# MCU.net
KiCad netlist of a schematic drawn in Altium Designer
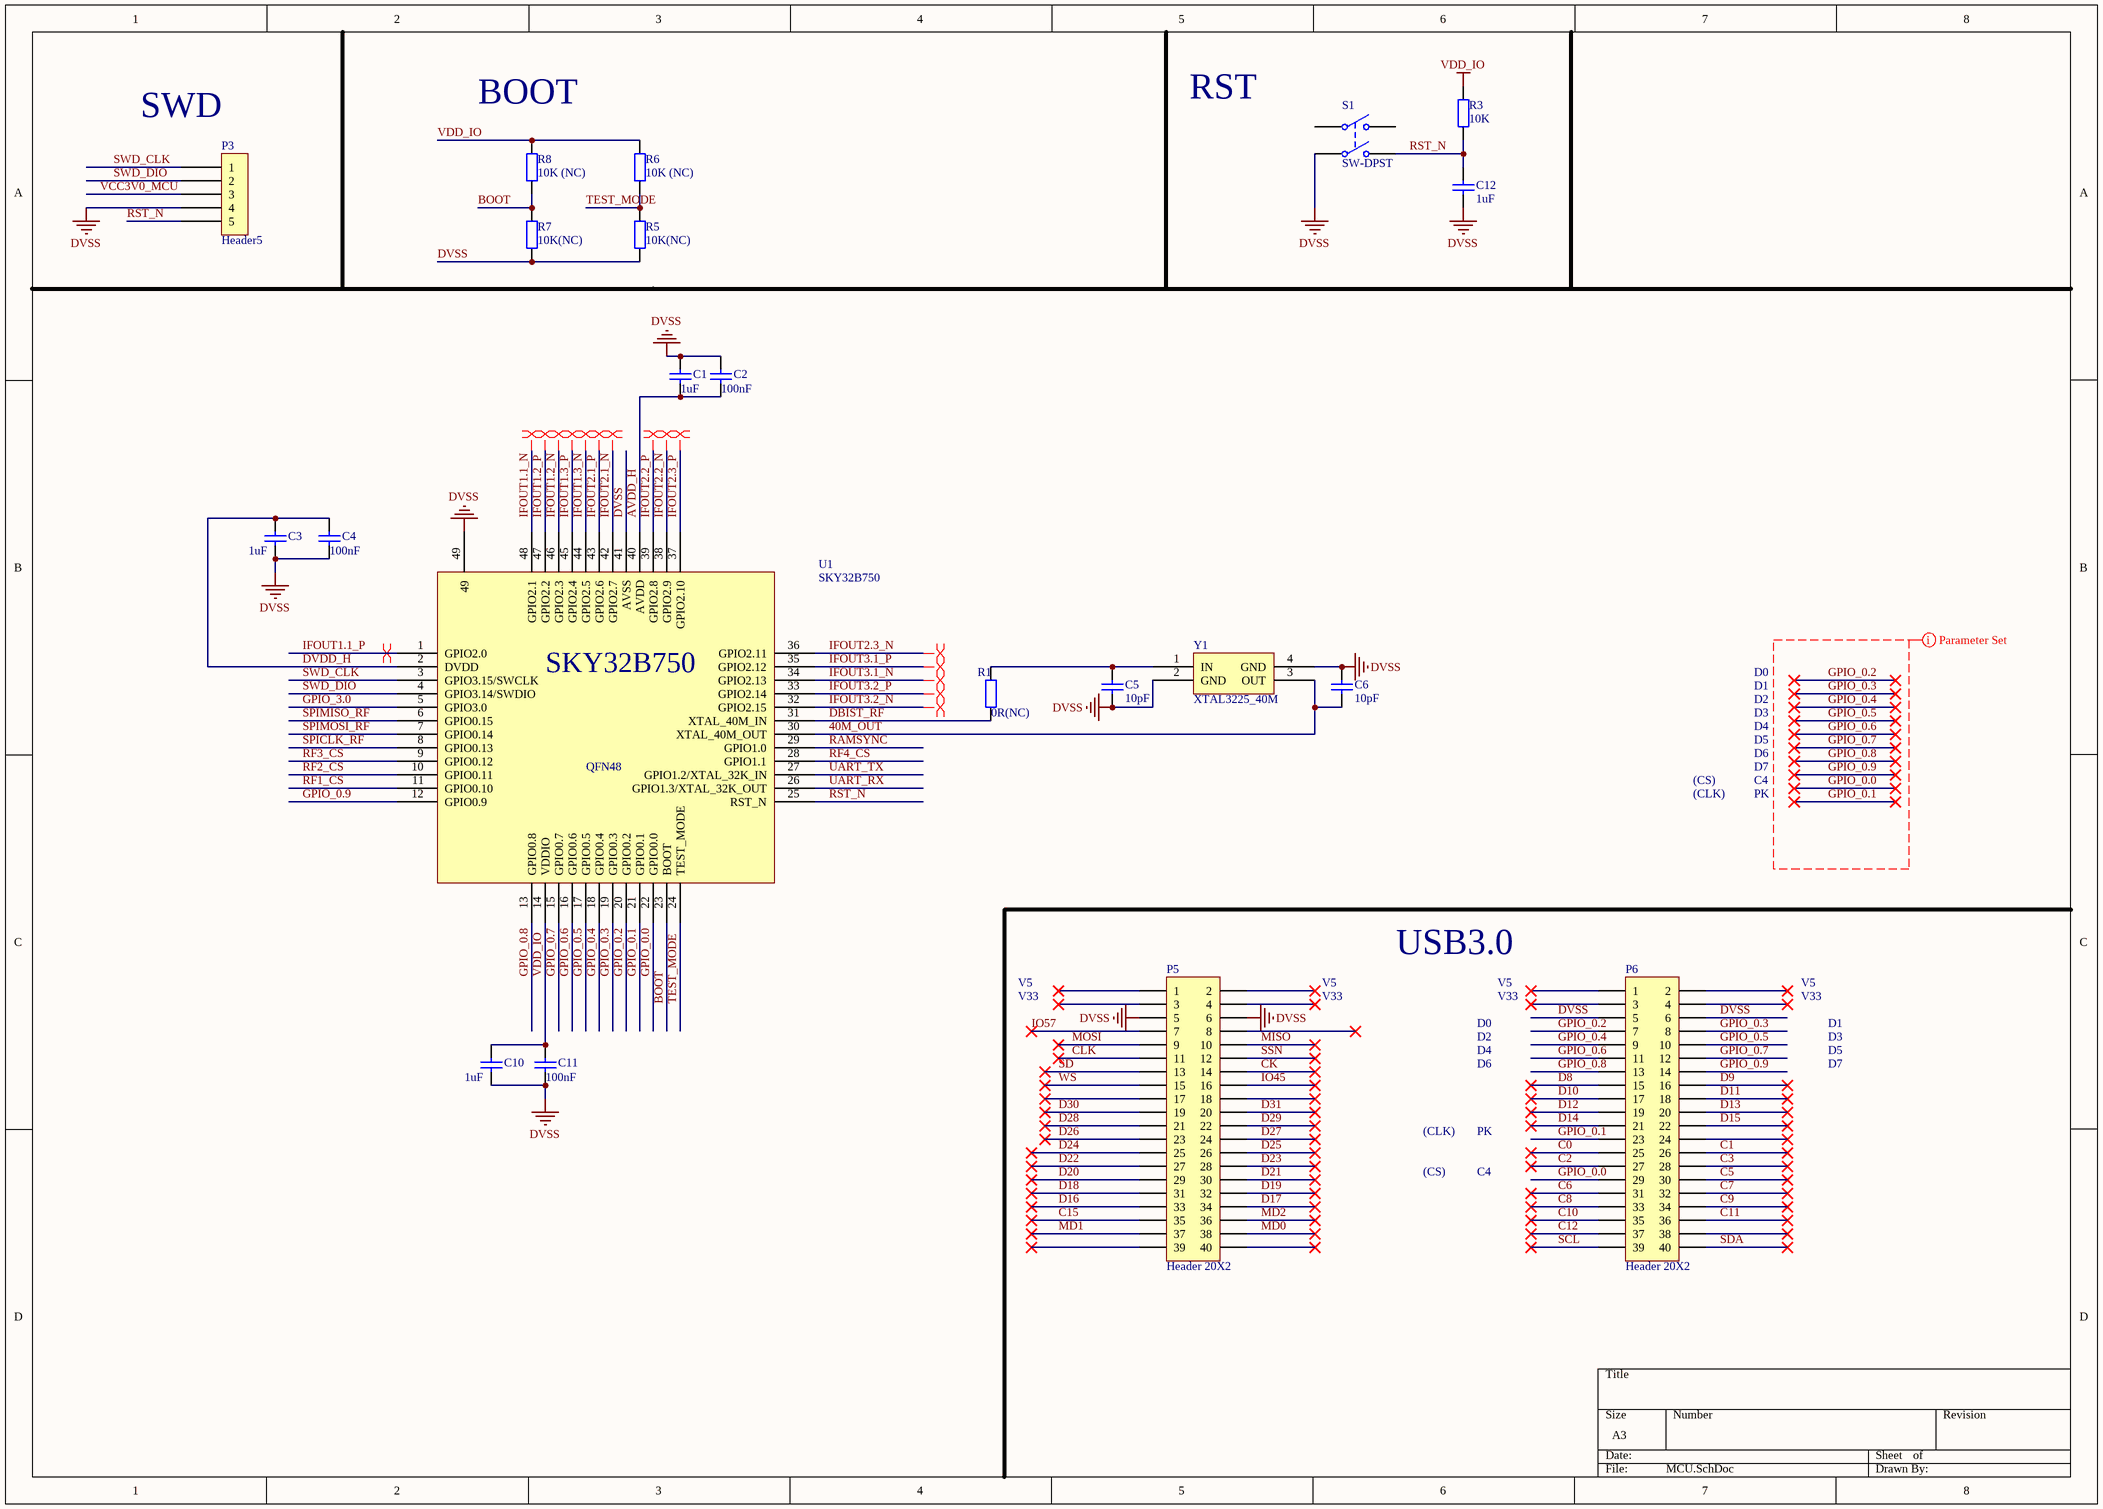
[diagram p0: MCU.SchDoc]

(export (version "E")
  (design (tool "Eeschema 10.0.6"))
  (components
    (comp (ref "C1")
      (value "1uF")
      (footprint "R0603")
      (description "CAP, CERM, 4.7nF, 100 V, +/- 5%, X7R, 0603")
      (fields (field (name "PUBLISHER") "Altium Limited"))
      (libsource (lib "SKY1311T-READER-V1.0_1") (part "Cap"))
    )
    (comp (ref "C2")
      (value "100nF")
      (footprint "R0603")
      (description "CAP, CERM, 4.7nF, 100 V, +/- 5%, X7R, 0603")
      (fields (field (name "PUBLISHER") "Altium Limited"))
      (libsource (lib "SKY1311T-READER-V1.0_1") (part "Cap"))
    )
    (comp (ref "C3")
      (value "1uF")
      (footprint "R0603")
      (description "CAP, CERM, 4.7nF, 100 V, +/- 5%, X7R, 0603")
      (fields (field (name "PUBLISHER") "Altium Limited"))
      (libsource (lib "SKY1311T-READER-V1.0_1") (part "Cap"))
    )
    (comp (ref "C4")
      (value "100nF")
      (footprint "R0603")
      (description "CAP, CERM, 4.7nF, 100 V, +/- 5%, X7R, 0603")
      (fields (field (name "PUBLISHER") "Altium Limited"))
      (libsource (lib "SKY1311T-READER-V1.0_1") (part "Cap"))
    )
    (comp (ref "C5")
      (value "10pF")
      (footprint "R0603")
      (description "Capacitor")
      (fields (field (name "PUBLISHER") "Altium Limited"))
      (libsource (lib "Miscellaneous Devices") (part "Cap"))
    )
    (comp (ref "C6")
      (value "10pF")
      (footprint "R0603")
      (description "Capacitor")
      (fields (field (name "PUBLISHER") "Altium Limited"))
      (libsource (lib "Miscellaneous Devices") (part "Cap"))
    )
    (comp (ref "C10")
      (value "1uF")
      (footprint "R0603")
      (description "CAP, CERM, 4.7nF, 100 V, +/- 5%, X7R, 0603")
      (fields (field (name "PUBLISHER") "Altium Limited"))
      (libsource (lib "SKY1311T-READER-V1.0_1") (part "Cap"))
    )
    (comp (ref "C11")
      (value "100nF")
      (footprint "R0603")
      (description "CAP, CERM, 4.7nF, 100 V, +/- 5%, X7R, 0603")
      (fields (field (name "PUBLISHER") "Altium Limited"))
      (libsource (lib "SKY1311T-READER-V1.0_1") (part "Cap"))
    )
    (comp (ref "C12")
      (value "1uF")
      (footprint "R0603")
      (description "Capacitor")
      (fields (field (name "PUBLISHER") "Altium Limited"))
      (libsource (lib "Miscellaneous Devices") (part "Cap"))
    )
    (comp (ref "P3")
      (value "Header5")
      (footprint "HDR1X5")
      (libsource (lib "SKY32B750_OSPI_EVB1_V2.0") (part "Header5"))
    )
    (comp (ref "P5")
      (value "Header 20X2")
      (footprint "2X20_2_54_SMD")
      (description "Header, 20-Pin, Dual row")
      (fields (field (name "PUBLISHER") "Altium Limited"))
      (libsource (lib "Miscellaneous Connectors") (part "Header 20X2"))
    )
    (comp (ref "P6")
      (value "Header 20X2")
      (footprint "2X20_2_54_SMD")
      (description "Header, 20-Pin, Dual row")
      (fields (field (name "PUBLISHER") "Altium Limited"))
      (libsource (lib "Miscellaneous Connectors") (part "Header 20X2"))
    )
    (comp (ref "R1")
      (value "0R(NC)")
      (footprint "R0603")
      (description "Resistor")
      (fields (field (name "PUBLISHER") "Altium Limited"))
      (libsource (lib "Miscellaneous Devices") (part "Res2"))
    )
    (comp (ref "R3")
      (value "10K")
      (footprint "R0603")
      (description "Resistor")
      (fields (field (name "PUBLISHER") "Altium Limited"))
      (libsource (lib "Miscellaneous Devices") (part "Res2"))
    )
    (comp (ref "R5")
      (value "10K(NC)")
      (footprint "R0603")
      (description "Resistor")
      (fields (field (name "PUBLISHER") "Altium Limited"))
      (libsource (lib "") (part "Res2_1"))
    )
    (comp (ref "R6")
      (value "10K (NC)")
      (footprint "R0603")
      (description "Resistor")
      (fields (field (name "PUBLISHER") "Altium Limited"))
      (libsource (lib "") (part "Res2_1"))
    )
    (comp (ref "R7")
      (value "10K(NC)")
      (footprint "R0603")
      (description "Resistor")
      (fields (field (name "PUBLISHER") "Altium Limited"))
      (libsource (lib "") (part "Res2_1"))
    )
    (comp (ref "R8")
      (value "10K (NC)")
      (footprint "R0603")
      (description "Resistor")
      (fields (field (name "PUBLISHER") "Altium Limited"))
      (libsource (lib "") (part "Res2_1"))
    )
    (comp (ref "S1")
      (value "SW-DPST")
      (footprint "sw")
      (description "Double-Pole, Single-Throw Switch")
      (fields (field (name "PUBLISHER") "Altium Limited"))
      (libsource (lib "Miscellaneous Devices") (part "SW-DPST"))
    )
    (comp (ref "U1")
      (value "SKY32B750")
      (footprint "QFN48")
      (libsource (lib "SKY32B750_OSPI_EVB1_V2.0") (part "SYK32B750"))
    )
    (comp (ref "Y1")
      (value "XTAL3225_40M")
      (footprint "XTAL-3225")
      (libsource (lib "Schlib1") (part "XTAL3225"))
    )
  )
  (nets
    (net (code "1") (name "/40M_OUT") (class "Default")
      (node (ref "C6") (pin "2") (pinfunction "2_2") (pintype "passive"))
      (node (ref "U1") (pin "30") (pinfunction "XTAL_40M_OUT_30") (pintype "passive"))
      (node (ref "Y1") (pin "3") (pinfunction "OUT_3") (pintype "passive"))
    )
    (net (code "2") (name "/AVDD_H") (class "Default")
      (node (ref "C1") (pin "1") (pinfunction "1_1") (pintype "passive"))
      (node (ref "C2") (pin "1") (pinfunction "1_1") (pintype "passive"))
      (node (ref "U1") (pin "40") (pinfunction "AVDD_40") (pintype "passive"))
    )
    (net (code "3") (name "/BOOT") (class "Default")
      (node (ref "R7") (pin "1") (pinfunction "1_1") (pintype "passive"))
      (node (ref "R8") (pin "2") (pinfunction "2_2") (pintype "passive"))
      (node (ref "U1") (pin "23") (pinfunction "BOOT_23") (pintype "passive"))
    )
    (net (code "4") (name "/C0") (class "Default")
      (node (ref "P6") (pin "25") (pinfunction "25_25") (pintype "passive+no_connect"))
    )
    (net (code "5") (name "/C1") (class "Default")
      (node (ref "P6") (pin "26") (pinfunction "26_26") (pintype "passive+no_connect"))
    )
    (net (code "6") (name "/C2") (class "Default")
      (node (ref "P6") (pin "27") (pinfunction "27_27") (pintype "passive+no_connect"))
    )
    (net (code "7") (name "/C3") (class "Default")
      (node (ref "P6") (pin "28") (pinfunction "28_28") (pintype "passive+no_connect"))
    )
    (net (code "8") (name "/C5") (class "Default")
      (node (ref "P6") (pin "30") (pinfunction "30_30") (pintype "passive+no_connect"))
    )
    (net (code "9") (name "/C6") (class "Default")
      (node (ref "P6") (pin "31") (pinfunction "31_31") (pintype "passive+no_connect"))
    )
    (net (code "10") (name "/C7") (class "Default")
      (node (ref "P6") (pin "32") (pinfunction "32_32") (pintype "passive+no_connect"))
    )
    (net (code "11") (name "/C8") (class "Default")
      (node (ref "P6") (pin "33") (pinfunction "33_33") (pintype "passive+no_connect"))
    )
    (net (code "12") (name "/C9") (class "Default")
      (node (ref "P6") (pin "34") (pinfunction "34_34") (pintype "passive+no_connect"))
    )
    (net (code "13") (name "/C10") (class "Default")
      (node (ref "P6") (pin "35") (pinfunction "35_35") (pintype "passive+no_connect"))
    )
    (net (code "14") (name "/C11") (class "Default")
      (node (ref "P6") (pin "36") (pinfunction "36_36") (pintype "passive+no_connect"))
    )
    (net (code "15") (name "/C12") (class "Default")
      (node (ref "P6") (pin "37") (pinfunction "37_37") (pintype "passive+no_connect"))
    )
    (net (code "16") (name "/C15") (class "Default")
      (node (ref "P5") (pin "35") (pinfunction "35_35") (pintype "passive+no_connect"))
    )
    (net (code "17") (name "/CK") (class "Default")
      (node (ref "P5") (pin "14") (pinfunction "14_14") (pintype "passive+no_connect"))
    )
    (net (code "18") (name "/CLK") (class "Default")
      (node (ref "P5") (pin "11") (pinfunction "11_11") (pintype "passive+no_connect"))
    )
    (net (code "19") (name "/D8") (class "Default")
      (node (ref "P6") (pin "15") (pinfunction "15_15") (pintype "passive+no_connect"))
    )
    (net (code "20") (name "/D9") (class "Default")
      (node (ref "P6") (pin "16") (pinfunction "16_16") (pintype "passive+no_connect"))
    )
    (net (code "21") (name "/D10") (class "Default")
      (node (ref "P6") (pin "17") (pinfunction "17_17") (pintype "passive+no_connect"))
    )
    (net (code "22") (name "/D11") (class "Default")
      (node (ref "P6") (pin "18") (pinfunction "18_18") (pintype "passive+no_connect"))
    )
    (net (code "23") (name "/D12") (class "Default")
      (node (ref "P6") (pin "19") (pinfunction "19_19") (pintype "passive+no_connect"))
    )
    (net (code "24") (name "/D13") (class "Default")
      (node (ref "P6") (pin "20") (pinfunction "20_20") (pintype "passive+no_connect"))
    )
    (net (code "25") (name "/D14") (class "Default")
      (node (ref "P6") (pin "21") (pinfunction "21_21") (pintype "passive+no_connect"))
    )
    (net (code "26") (name "/D15") (class "Default")
      (node (ref "P6") (pin "22") (pinfunction "22_22") (pintype "passive+no_connect"))
    )
    (net (code "27") (name "/D16") (class "Default")
      (node (ref "P5") (pin "33") (pinfunction "33_33") (pintype "passive+no_connect"))
    )
    (net (code "28") (name "/D17") (class "Default")
      (node (ref "P5") (pin "34") (pinfunction "34_34") (pintype "passive+no_connect"))
    )
    (net (code "29") (name "/D18") (class "Default")
      (node (ref "P5") (pin "31") (pinfunction "31_31") (pintype "passive+no_connect"))
    )
    (net (code "30") (name "/D19") (class "Default")
      (node (ref "P5") (pin "32") (pinfunction "32_32") (pintype "passive+no_connect"))
    )
    (net (code "31") (name "/D20") (class "Default")
      (node (ref "P5") (pin "29") (pinfunction "29_29") (pintype "passive+no_connect"))
    )
    (net (code "32") (name "/D21") (class "Default")
      (node (ref "P5") (pin "30") (pinfunction "30_30") (pintype "passive+no_connect"))
    )
    (net (code "33") (name "/D22") (class "Default")
      (node (ref "P5") (pin "27") (pinfunction "27_27") (pintype "passive+no_connect"))
    )
    (net (code "34") (name "/D23") (class "Default")
      (node (ref "P5") (pin "28") (pinfunction "28_28") (pintype "passive+no_connect"))
    )
    (net (code "35") (name "/D24") (class "Default")
      (node (ref "P5") (pin "25") (pinfunction "25_25") (pintype "passive+no_connect"))
    )
    (net (code "36") (name "/D25") (class "Default")
      (node (ref "P5") (pin "26") (pinfunction "26_26") (pintype "passive+no_connect"))
    )
    (net (code "37") (name "/D26") (class "Default")
      (node (ref "P5") (pin "23") (pinfunction "23_23") (pintype "passive+no_connect"))
    )
    (net (code "38") (name "/D27") (class "Default")
      (node (ref "P5") (pin "24") (pinfunction "24_24") (pintype "passive+no_connect"))
    )
    (net (code "39") (name "/D28") (class "Default")
      (node (ref "P5") (pin "21") (pinfunction "21_21") (pintype "passive+no_connect"))
    )
    (net (code "40") (name "/D29") (class "Default")
      (node (ref "P5") (pin "22") (pinfunction "22_22") (pintype "passive+no_connect"))
    )
    (net (code "41") (name "/D30") (class "Default")
      (node (ref "P5") (pin "19") (pinfunction "19_19") (pintype "passive+no_connect"))
    )
    (net (code "42") (name "/D31") (class "Default")
      (node (ref "P5") (pin "20") (pinfunction "20_20") (pintype "passive+no_connect"))
    )
    (net (code "43") (name "/DBIST_RF") (class "Default")
      (node (ref "R1") (pin "1") (pinfunction "1_1") (pintype "passive"))
      (node (ref "U1") (pin "31") (pinfunction "XTAL_40M_IN_31") (pintype "passive"))
    )
    (net (code "44") (name "/DVDD_H") (class "Default")
      (node (ref "C3") (pin "2") (pinfunction "2_2") (pintype "passive"))
      (node (ref "C4") (pin "2") (pinfunction "2_2") (pintype "passive"))
      (node (ref "U1") (pin "2") (pinfunction "DVDD_2") (pintype "passive"))
    )
    (net (code "45") (name "/GPIO_0.0") (class "Default")
      (node (ref "P6") (pin "29") (pinfunction "29_29") (pintype "passive"))
      (node (ref "U1") (pin "22") (pinfunction "GPIO0.0_22") (pintype "passive"))
    )
    (net (code "46") (name "/GPIO_0.1") (class "Default")
      (node (ref "P6") (pin "23") (pinfunction "23_23") (pintype "passive"))
      (node (ref "U1") (pin "21") (pinfunction "GPIO0.1_21") (pintype "passive"))
    )
    (net (code "47") (name "/GPIO_0.2") (class "Default")
      (node (ref "P6") (pin "7") (pinfunction "7_7") (pintype "passive"))
      (node (ref "U1") (pin "20") (pinfunction "GPIO0.2_20") (pintype "passive"))
    )
    (net (code "48") (name "/GPIO_0.3") (class "Default")
      (node (ref "P6") (pin "8") (pinfunction "8_8") (pintype "passive"))
      (node (ref "U1") (pin "19") (pinfunction "GPIO0.3_19") (pintype "passive"))
    )
    (net (code "49") (name "/GPIO_0.4") (class "Default")
      (node (ref "P6") (pin "9") (pinfunction "9_9") (pintype "passive"))
      (node (ref "U1") (pin "18") (pinfunction "GPIO0.4_18") (pintype "passive"))
    )
    (net (code "50") (name "/GPIO_0.5") (class "Default")
      (node (ref "P6") (pin "10") (pinfunction "10_10") (pintype "passive"))
      (node (ref "U1") (pin "17") (pinfunction "GPIO0.5_17") (pintype "passive"))
    )
    (net (code "51") (name "/GPIO_0.6") (class "Default")
      (node (ref "P6") (pin "11") (pinfunction "11_11") (pintype "passive"))
      (node (ref "U1") (pin "16") (pinfunction "GPIO0.6_16") (pintype "passive"))
    )
    (net (code "52") (name "/GPIO_0.7") (class "Default")
      (node (ref "P6") (pin "12") (pinfunction "12_12") (pintype "passive"))
      (node (ref "U1") (pin "15") (pinfunction "GPIO0.7_15") (pintype "passive"))
    )
    (net (code "53") (name "/GPIO_0.8") (class "Default")
      (node (ref "P6") (pin "13") (pinfunction "13_13") (pintype "passive"))
      (node (ref "U1") (pin "13") (pinfunction "GPIO0.8_13") (pintype "passive"))
    )
    (net (code "54") (name "/GPIO_0.9") (class "Default")
      (node (ref "P6") (pin "14") (pinfunction "14_14") (pintype "passive"))
      (node (ref "U1") (pin "12") (pinfunction "GPIO0.9_12") (pintype "passive"))
    )
    (net (code "55") (name "/GPIO_3.0") (class "Default")
      (node (ref "U1") (pin "5") (pinfunction "GPIO3.0_5") (pintype "passive"))
    )
    (net (code "56") (name "/IFOUT1.1_N") (class "Default")
      (node (ref "U1") (pin "48") (pinfunction "GPIO2.1_48") (pintype "passive"))
    )
    (net (code "57") (name "/IFOUT1.1_P") (class "Default")
      (node (ref "U1") (pin "1") (pinfunction "GPIO2.0_1") (pintype "passive"))
    )
    (net (code "58") (name "/IFOUT1.2_N") (class "Default")
      (node (ref "U1") (pin "46") (pinfunction "GPIO2.3_46") (pintype "passive"))
    )
    (net (code "59") (name "/IFOUT1.2_P") (class "Default")
      (node (ref "U1") (pin "47") (pinfunction "GPIO2.2_47") (pintype "passive"))
    )
    (net (code "60") (name "/IFOUT1.3_N") (class "Default")
      (node (ref "U1") (pin "44") (pinfunction "GPIO2.5_44") (pintype "passive"))
    )
    (net (code "61") (name "/IFOUT1.3_P") (class "Default")
      (node (ref "U1") (pin "45") (pinfunction "GPIO2.4_45") (pintype "passive"))
    )
    (net (code "62") (name "/IFOUT2.1_N") (class "Default")
      (node (ref "U1") (pin "42") (pinfunction "GPIO2.7_42") (pintype "passive"))
    )
    (net (code "63") (name "/IFOUT2.1_P") (class "Default")
      (node (ref "U1") (pin "43") (pinfunction "GPIO2.6_43") (pintype "passive"))
    )
    (net (code "64") (name "/IFOUT2.2_N") (class "Default")
      (node (ref "U1") (pin "38") (pinfunction "GPIO2.9_38") (pintype "passive"))
    )
    (net (code "65") (name "/IFOUT2.2_P") (class "Default")
      (node (ref "U1") (pin "39") (pinfunction "GPIO2.8_39") (pintype "passive"))
    )
    (net (code "66") (name "/IFOUT2.3_N") (class "Default")
      (node (ref "U1") (pin "36") (pinfunction "GPIO2.11_36") (pintype "passive"))
    )
    (net (code "67") (name "/IFOUT2.3_P") (class "Default")
      (node (ref "U1") (pin "37") (pinfunction "GPIO2.10_37") (pintype "passive"))
    )
    (net (code "68") (name "/IFOUT3.1_N") (class "Default")
      (node (ref "U1") (pin "34") (pinfunction "GPIO2.13_34") (pintype "passive"))
    )
    (net (code "69") (name "/IFOUT3.1_P") (class "Default")
      (node (ref "U1") (pin "35") (pinfunction "GPIO2.12_35") (pintype "passive"))
    )
    (net (code "70") (name "/IFOUT3.2_N") (class "Default")
      (node (ref "U1") (pin "32") (pinfunction "GPIO2.15_32") (pintype "passive"))
    )
    (net (code "71") (name "/IFOUT3.2_P") (class "Default")
      (node (ref "U1") (pin "33") (pinfunction "GPIO2.14_33") (pintype "passive"))
    )
    (net (code "72") (name "/IO45") (class "Default")
      (node (ref "P5") (pin "16") (pinfunction "16_16") (pintype "passive+no_connect"))
    )
    (net (code "73") (name "/IO57") (class "Default")
      (node (ref "P5") (pin "7") (pinfunction "7_7") (pintype "passive+no_connect"))
    )
    (net (code "74") (name "/MD0") (class "Default")
      (node (ref "P5") (pin "38") (pinfunction "38_38") (pintype "passive+no_connect"))
    )
    (net (code "75") (name "/MD1") (class "Default")
      (node (ref "P5") (pin "37") (pinfunction "37_37") (pintype "passive+no_connect"))
    )
    (net (code "76") (name "/MD2") (class "Default")
      (node (ref "P5") (pin "36") (pinfunction "36_36") (pintype "passive+no_connect"))
    )
    (net (code "77") (name "/MISO") (class "Default")
      (node (ref "P5") (pin "10") (pinfunction "10_10") (pintype "passive+no_connect"))
    )
    (net (code "78") (name "/MOSI") (class "Default")
      (node (ref "P5") (pin "9") (pinfunction "9_9") (pintype "passive+no_connect"))
    )
    (net (code "79") (name "/RAMSYNC") (class "Default")
      (node (ref "U1") (pin "29") (pinfunction "GPIO1.0_29") (pintype "passive"))
    )
    (net (code "80") (name "/RF1_CS") (class "Default")
      (node (ref "U1") (pin "11") (pinfunction "GPIO0.10_11") (pintype "passive"))
    )
    (net (code "81") (name "/RF2_CS") (class "Default")
      (node (ref "U1") (pin "10") (pinfunction "GPIO0.11_10") (pintype "passive"))
    )
    (net (code "82") (name "/RF3_CS") (class "Default")
      (node (ref "U1") (pin "9") (pinfunction "GPIO0.12_9") (pintype "passive"))
    )
    (net (code "83") (name "/RF4_CS") (class "Default")
      (node (ref "U1") (pin "28") (pinfunction "GPIO1.1_28") (pintype "passive"))
    )
    (net (code "84") (name "/RST_N") (class "Default")
      (node (ref "C12") (pin "2") (pinfunction "2_2") (pintype "passive"))
      (node (ref "P3") (pin "5") (pinfunction "5_5") (pintype "passive"))
      (node (ref "R3") (pin "1") (pinfunction "1_1") (pintype "passive"))
      (node (ref "S1") (pin "4") (pinfunction "NO2_4") (pintype "passive"))
      (node (ref "U1") (pin "25") (pinfunction "RST_N_25") (pintype "passive"))
    )
    (net (code "85") (name "/SCL") (class "Default")
      (node (ref "P6") (pin "39") (pinfunction "39_39") (pintype "passive+no_connect"))
    )
    (net (code "86") (name "/SD") (class "Default")
      (node (ref "P5") (pin "13") (pinfunction "13_13") (pintype "passive+no_connect"))
    )
    (net (code "87") (name "/SDA") (class "Default")
      (node (ref "P6") (pin "40") (pinfunction "40_40") (pintype "passive+no_connect"))
    )
    (net (code "88") (name "/SPICLK_RF") (class "Default")
      (node (ref "U1") (pin "8") (pinfunction "GPIO0.13_8") (pintype "passive"))
    )
    (net (code "89") (name "/SPIMISO_RF") (class "Default")
      (node (ref "U1") (pin "6") (pinfunction "GPIO0.15_6") (pintype "passive"))
    )
    (net (code "90") (name "/SPIMOSI_RF") (class "Default")
      (node (ref "U1") (pin "7") (pinfunction "GPIO0.14_7") (pintype "passive"))
    )
    (net (code "91") (name "/SSN") (class "Default")
      (node (ref "P5") (pin "12") (pinfunction "12_12") (pintype "passive+no_connect"))
    )
    (net (code "92") (name "/SWD_CLK") (class "Default")
      (node (ref "P3") (pin "1") (pinfunction "1_1") (pintype "passive"))
      (node (ref "U1") (pin "3") (pinfunction "GPIO3.15/SWCLK_3") (pintype "passive"))
    )
    (net (code "93") (name "/SWD_DIO") (class "Default")
      (node (ref "P3") (pin "2") (pinfunction "2_2") (pintype "passive"))
      (node (ref "U1") (pin "4") (pinfunction "GPIO3.14/SWDIO_4") (pintype "passive"))
    )
    (net (code "94") (name "/TEST_MODE") (class "Default")
      (node (ref "R5") (pin "1") (pinfunction "1_1") (pintype "passive"))
      (node (ref "R6") (pin "2") (pinfunction "2_2") (pintype "passive"))
      (node (ref "U1") (pin "24") (pinfunction "TEST_MODE_24") (pintype "passive"))
    )
    (net (code "95") (name "/UART_RX") (class "Default")
      (node (ref "U1") (pin "26") (pinfunction "GPIO1.3/XTAL_32K_OUT_26") (pintype "passive"))
    )
    (net (code "96") (name "/UART_TX") (class "Default")
      (node (ref "U1") (pin "27") (pinfunction "GPIO1.2/XTAL_32K_IN_27") (pintype "passive"))
    )
    (net (code "97") (name "/VCC3V0_MCU") (class "Default")
      (node (ref "P3") (pin "3") (pinfunction "3_3") (pintype "passive"))
    )
    (net (code "98") (name "/WS") (class "Default")
      (node (ref "P5") (pin "15") (pinfunction "15_15") (pintype "passive+no_connect"))
    )
    (net (code "99") (name "DVSS") (class "Default")
      (node (ref "C1") (pin "2") (pinfunction "2_2") (pintype "passive"))
      (node (ref "C10") (pin "1") (pinfunction "1_1") (pintype "passive"))
      (node (ref "C11") (pin "1") (pinfunction "1_1") (pintype "passive"))
      (node (ref "C12") (pin "1") (pinfunction "1_1") (pintype "passive"))
      (node (ref "C2") (pin "2") (pinfunction "2_2") (pintype "passive"))
      (node (ref "C3") (pin "1") (pinfunction "1_1") (pintype "passive"))
      (node (ref "C4") (pin "1") (pinfunction "1_1") (pintype "passive"))
      (node (ref "C5") (pin "2") (pinfunction "2_2") (pintype "passive"))
      (node (ref "C6") (pin "1") (pinfunction "1_1") (pintype "passive"))
      (node (ref "P3") (pin "4") (pinfunction "4_4") (pintype "passive"))
      (node (ref "P5") (pin "5") (pinfunction "5_5") (pintype "passive"))
      (node (ref "P5") (pin "6") (pinfunction "6_6") (pintype "passive"))
      (node (ref "P6") (pin "5") (pinfunction "5_5") (pintype "passive"))
      (node (ref "P6") (pin "6") (pinfunction "6_6") (pintype "passive"))
      (node (ref "R5") (pin "2") (pinfunction "2_2") (pintype "passive"))
      (node (ref "R7") (pin "2") (pinfunction "2_2") (pintype "passive"))
      (node (ref "S1") (pin "3") (pinfunction "COMMON2_3") (pintype "passive"))
      (node (ref "U1") (pin "41") (pinfunction "AVSS_41") (pintype "passive"))
      (node (ref "U1") (pin "49") (pinfunction "49_49") (pintype "passive"))
      (node (ref "Y1") (pin "2") (pinfunction "GND_2") (pintype "passive"))
      (node (ref "Y1") (pin "4") (pinfunction "GND_4") (pintype "passive"))
    )
    (net (code "100") (name "Net-(Y1-IN)") (class "Default")
      (node (ref "C5") (pin "1") (pinfunction "1_1") (pintype "passive"))
      (node (ref "R1") (pin "2") (pinfunction "2_2") (pintype "passive"))
      (node (ref "Y1") (pin "1") (pinfunction "IN_1") (pintype "passive"))
    )
    (net (code "101") (name "VDD_IO") (class "Default")
      (node (ref "C10") (pin "2") (pinfunction "2_2") (pintype "passive"))
      (node (ref "C11") (pin "2") (pinfunction "2_2") (pintype "passive"))
      (node (ref "R3") (pin "2") (pinfunction "2_2") (pintype "passive"))
      (node (ref "R6") (pin "1") (pinfunction "1_1") (pintype "passive"))
      (node (ref "R8") (pin "1") (pinfunction "1_1") (pintype "passive"))
      (node (ref "U1") (pin "14") (pinfunction "VDDIO_14") (pintype "passive"))
    )
    (net (code "102") (name "unconnected-(P5-Pad1)") (class "Default")
      (node (ref "P5") (pin "1") (pinfunction "1_1") (pintype "passive+no_connect"))
    )
    (net (code "103") (name "unconnected-(P5-Pad2)") (class "Default")
      (node (ref "P5") (pin "2") (pinfunction "2_2") (pintype "passive+no_connect"))
    )
    (net (code "104") (name "unconnected-(P5-Pad3)") (class "Default")
      (node (ref "P5") (pin "3") (pinfunction "3_3") (pintype "passive+no_connect"))
    )
    (net (code "105") (name "unconnected-(P5-Pad4)") (class "Default")
      (node (ref "P5") (pin "4") (pinfunction "4_4") (pintype "passive+no_connect"))
    )
    (net (code "106") (name "unconnected-(P5-Pad8)") (class "Default")
      (node (ref "P5") (pin "8") (pinfunction "8_8") (pintype "passive+no_connect"))
    )
    (net (code "107") (name "unconnected-(P5-Pad17)") (class "Default")
      (node (ref "P5") (pin "17") (pinfunction "17_17") (pintype "passive+no_connect"))
    )
    (net (code "108") (name "unconnected-(P5-Pad18)") (class "Default")
      (node (ref "P5") (pin "18") (pinfunction "18_18") (pintype "passive+no_connect"))
    )
    (net (code "109") (name "unconnected-(P5-Pad39)") (class "Default")
      (node (ref "P5") (pin "39") (pinfunction "39_39") (pintype "passive+no_connect"))
    )
    (net (code "110") (name "unconnected-(P5-Pad40)") (class "Default")
      (node (ref "P5") (pin "40") (pinfunction "40_40") (pintype "passive+no_connect"))
    )
    (net (code "111") (name "unconnected-(P6-Pad1)") (class "Default")
      (node (ref "P6") (pin "1") (pinfunction "1_1") (pintype "passive+no_connect"))
    )
    (net (code "112") (name "unconnected-(P6-Pad2)") (class "Default")
      (node (ref "P6") (pin "2") (pinfunction "2_2") (pintype "passive+no_connect"))
    )
    (net (code "113") (name "unconnected-(P6-Pad3)") (class "Default")
      (node (ref "P6") (pin "3") (pinfunction "3_3") (pintype "passive+no_connect"))
    )
    (net (code "114") (name "unconnected-(P6-Pad4)") (class "Default")
      (node (ref "P6") (pin "4") (pinfunction "4_4") (pintype "passive+no_connect"))
    )
    (net (code "115") (name "unconnected-(P6-Pad24)") (class "Default")
      (node (ref "P6") (pin "24") (pinfunction "24_24") (pintype "passive+no_connect"))
    )
    (net (code "116") (name "unconnected-(P6-Pad38)") (class "Default")
      (node (ref "P6") (pin "38") (pinfunction "38_38") (pintype "passive+no_connect"))
    )
    (net (code "117") (name "unconnected-(S1-COMMON1-Pad1)") (class "Default")
      (node (ref "S1") (pin "1") (pinfunction "COMMON1_1") (pintype "passive"))
    )
    (net (code "118") (name "unconnected-(S1-NO1-Pad2)") (class "Default")
      (node (ref "S1") (pin "2") (pinfunction "NO1_2") (pintype "passive"))
    )
  )
)
